# filter-9.net
KiCad netlist of a schematic drawn in Altium Designer
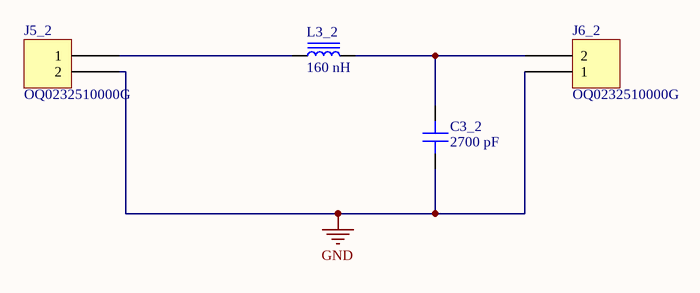
[diagram p0: filter-9.SchDoc]

(export (version "E")
  (design (tool "Eeschema 10.0.6"))
  (components
    (comp (ref "C3_2")
      (value "2700 pF")
      (footprint "CAP 0603_1608")
      (description "CAP CER 2700PF 25V NP0 0603")
      (fields (field (name "PART NUMBER") "C0603C272F3GAC7867") (field (name "MANUFACTURER") "KEMET"))
      (libsource (lib "Celestial Altium Library - altium_library") (part "Capacitor"))
    )
    (comp (ref "J5_2")
      (value "OQ0232510000G")
      (footprint "FCI 06-381-2PIN")
      (description "TERM BLOCK HDR 2POS 90DEG 3.81MM")
      (fields (field (name "MANUFACTURER") "Amphenol Anytek"))
      (libsource (lib "Celestial Altium Library - altium_library") (part "2 Pin"))
    )
    (comp (ref "J6_2")
      (value "OQ0232510000G")
      (footprint "FCI 06-381-2PIN")
      (description "TERM BLOCK HDR 2POS 90DEG 3.81MM")
      (fields (field (name "MANUFACTURER") "Amphenol Anytek"))
      (libsource (lib "") (part "2 Pin_1"))
    )
    (comp (ref "L3_2")
      (value "160 nH")
      (footprint "IND 0402_1005 RF WW")
      (description "FIXED IND 160NH 480MA 330MOHM SM")
      (fields
        (field (name "PART NUMBER") "LQW15CNR16J00D")
        (field (name "MANUFACTURER") "Murata Electronics")
      )
      (libsource (lib "Celestial Altium Library - altium_library") (part "Inductor"))
    )
  )
  (nets
    (net (code "1") (name "GND") (class "Default")
      (node (ref "C3_2") (pin "1") (pinfunction "1_1") (pintype "passive"))
      (node (ref "J5_2") (pin "2") (pinfunction "2_2") (pintype "passive"))
      (node (ref "J6_2") (pin "1") (pinfunction "1_1") (pintype "passive"))
    )
    (net (code "2") (name "Net-(C3_2-Pad2)") (class "Default")
      (node (ref "C3_2") (pin "2") (pinfunction "2_2") (pintype "passive"))
      (node (ref "J6_2") (pin "2") (pinfunction "2_2") (pintype "passive"))
      (node (ref "L3_2") (pin "2") (pinfunction "2_2") (pintype "passive"))
    )
    (net (code "3") (name "Net-(J5_2-Pad1)") (class "Default")
      (node (ref "J5_2") (pin "1") (pinfunction "1_1") (pintype "passive"))
      (node (ref "L3_2") (pin "1") (pinfunction "1_1") (pintype "passive"))
    )
  )
)
